# Node_Water.net
KiCad netlist of a schematic drawn in Altium Designer
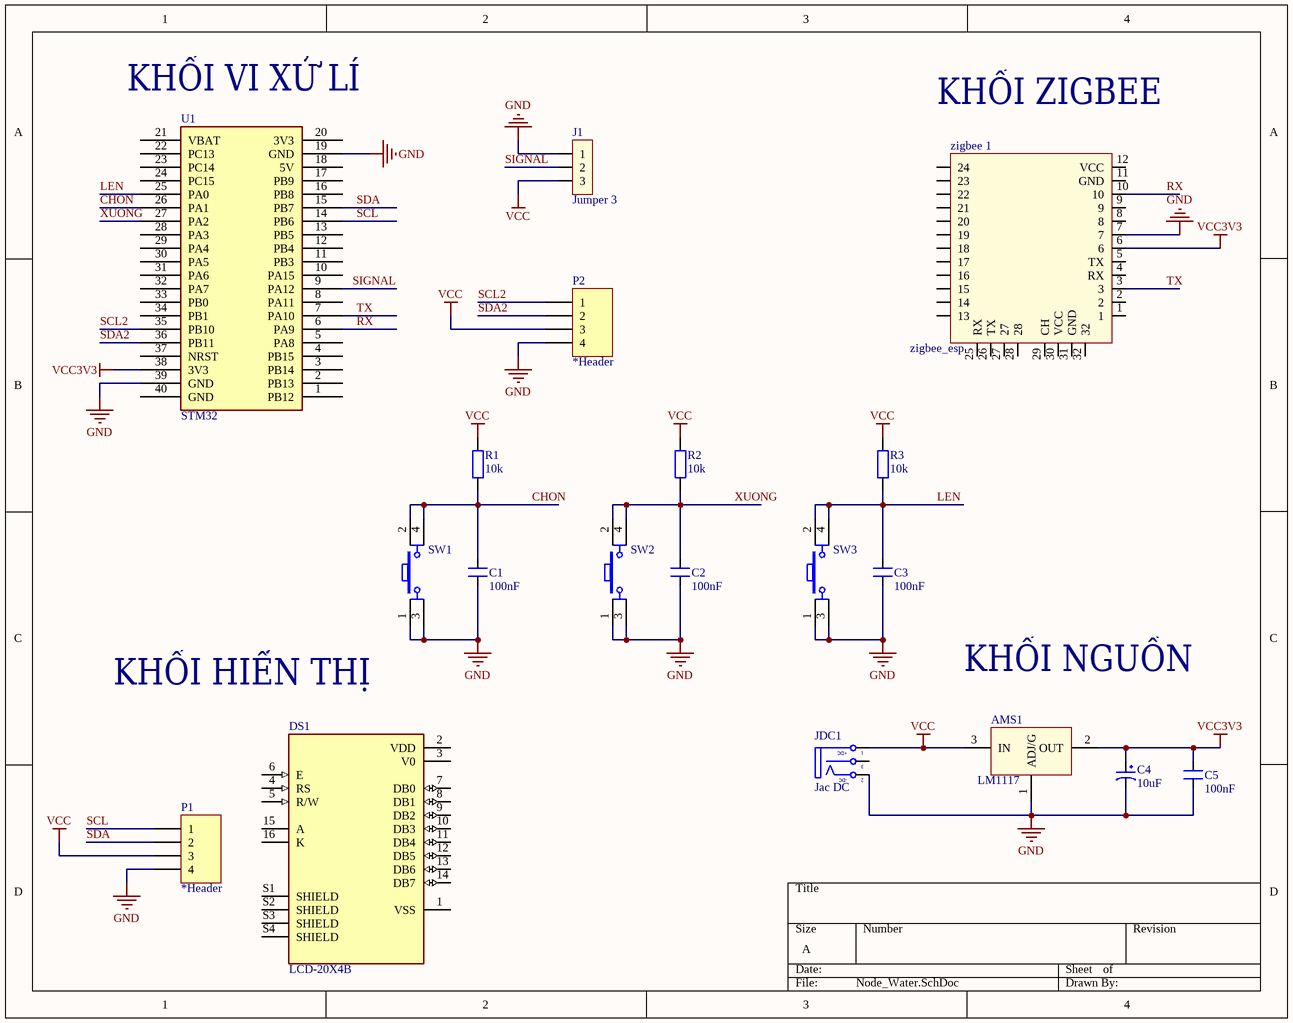
[diagram p0: Node_Water.SchDoc]

(export (version "E")
  (design (tool "Eeschema 10.0.6"))
  (components
    (comp (ref "AMS1")
      (value "LM1117")
      (footprint "SOT223-4N")
      (description "Available in 1.8V, 2.5V, 2.85V, 3.3V, 5V, and  Adjustable Versions")
      (libsource (lib "ACtoDC") (part "LM1117"))
    )
    (comp (ref "C1")
      (value "100nF")
      (footprint "CN1")
      (description "Cremic For Xtal 1pF => 100pF")
      (libsource (lib "syhaunguyen") (part "CN0"))
    )
    (comp (ref "C2")
      (value "100nF")
      (footprint "CN1")
      (description "Cremic For Xtal 1pF => 100pF")
      (libsource (lib "syhaunguyen") (part "CN0"))
    )
    (comp (ref "C3")
      (value "100nF")
      (footprint "CN1")
      (description "Cremic For Xtal 1pF => 100pF")
      (libsource (lib "syhaunguyen") (part "CN0"))
    )
    (comp (ref "C4")
      (value "10uF")
      (footprint "CP1/2")
      (description "Cap P  0,1uF < 22uF , 16 - 50V")
      (libsource (lib "VioletofSun") (part "CP1"))
    )
    (comp (ref "C5")
      (value "100nF")
      (footprint "CN1")
      (description "Cremic For Xtal 1pF => 100pF")
      (libsource (lib "syhaunguyen") (part "CN0"))
    )
    (comp (ref "DS1")
      (value "LCD-20X4B")
      (footprint "LCD_LCD-20X4B")
      (description "Display Development Tools 20X4 CHARACTER BLUE LCD W/BACKLIGHT")
      (fields (field (name "MF") "Gravitech"))
      (libsource (lib "LCD-20X4B") (part "LCD-20X4B"))
    )
    (comp (ref "J1") (value "Jumper 3") (footprint "JP3") (libsource (lib "syhaunguyen") (part "JP3")))
    (comp (ref "JDC1")
      (value "Jac DC")
      (footprint "DC-IN")
      (description "Jac DC input")
      (libsource (lib "syhaunguyen") (part "DCIN"))
    )
    (comp (ref "P1")
      (value "*Header")
      (footprint "HDR1X4")
      (description "Header, 4-Pin, Right Angle")
      (fields (field (name "PUBLISHER") "Altium Limited"))
      (libsource (lib "Cty1") (part "Header 4"))
    )
    (comp (ref "P2")
      (value "*Header")
      (footprint "HDR1X4")
      (description "Header, 4-Pin, Right Angle")
      (fields (field (name "PUBLISHER") "Altium Limited"))
      (libsource (lib "Cty1") (part "Header 4"))
    )
    (comp (ref "R1")
      (value "10k")
      (footprint "R1/4W")
      (description "Resistor 1/4W")
      (libsource (lib "syhaunguyen") (part "R1/4W"))
    )
    (comp (ref "R2")
      (value "10k")
      (footprint "R1/4W")
      (description "Resistor 1/4W")
      (libsource (lib "syhaunguyen") (part "R1/4W"))
    )
    (comp (ref "R3")
      (value "10k")
      (footprint "R1/4W")
      (description "Resistor 1/4W")
      (libsource (lib "syhaunguyen") (part "R1/4W"))
    )
    (comp (ref "SW1")
      (value "SW")
      (footprint "SW4")
      (description "Switch button 4 pin")
      (libsource (lib "syhaunguyen") (part "SW4"))
    )
    (comp (ref "SW2")
      (value "SW")
      (footprint "SW4")
      (description "Switch button 4 pin")
      (libsource (lib "syhaunguyen") (part "SW4"))
    )
    (comp (ref "SW3")
      (value "SW")
      (footprint "SW4")
      (description "Switch button 4 pin")
      (libsource (lib "syhaunguyen") (part "SW4"))
    )
    (comp (ref "U1")
      (value "STM32")
      (footprint "STM32")
      (libsource (lib "Other Microcontrollers") (part "STM32"))
    )
    (comp (ref "zigbee 1")
      (value "zigbee_esp")
      (footprint "zigbee")
      (libsource (lib "Main_stm8") (part "zigbee_esp"))
    )
  )
  (nets
    (net (code "2") (name "/CHON") (class "Default")
      (node (ref "C1") (pin "2") (pinfunction "2_2") (pintype "passive"))
      (node (ref "R1") (pin "1") (pinfunction "1_1") (pintype "passive"))
      (node (ref "SW1") (pin "2") (pintype "passive"))
      (node (ref "SW1") (pin "4") (pintype "passive"))
      (node (ref "U1") (pin "26") (pinfunction "PA1_26") (pintype "passive"))
    )
    (net (code "3") (name "/LEN") (class "Default")
      (node (ref "C3") (pin "2") (pinfunction "2_2") (pintype "passive"))
      (node (ref "R3") (pin "1") (pinfunction "1_1") (pintype "passive"))
      (node (ref "SW3") (pin "2") (pintype "passive"))
      (node (ref "SW3") (pin "4") (pintype "passive"))
      (node (ref "U1") (pin "25") (pinfunction "PA0_25") (pintype "passive"))
    )
    (net (code "4") (name "/RX") (class "Default")
      (node (ref "U1") (pin "6") (pinfunction "PA9_6") (pintype "passive"))
      (node (ref "zigbee 1") (pin "10") (pinfunction "10_10") (pintype "passive"))
    )
    (net (code "5") (name "/SCL") (class "Default")
      (node (ref "P1") (pin "1") (pinfunction "1_1") (pintype "passive"))
      (node (ref "U1") (pin "14") (pinfunction "PB6_14") (pintype "passive"))
    )
    (net (code "6") (name "/SCL2") (class "Default")
      (node (ref "P2") (pin "1") (pinfunction "1_1") (pintype "passive"))
      (node (ref "U1") (pin "35") (pinfunction "PB10_35") (pintype "passive"))
    )
    (net (code "7") (name "/SDA") (class "Default")
      (node (ref "P1") (pin "2") (pinfunction "2_2") (pintype "passive"))
      (node (ref "U1") (pin "15") (pinfunction "PB7_15") (pintype "passive"))
    )
    (net (code "8") (name "/SDA2") (class "Default")
      (node (ref "P2") (pin "2") (pinfunction "2_2") (pintype "passive"))
      (node (ref "U1") (pin "36") (pinfunction "PB11_36") (pintype "passive"))
    )
    (net (code "9") (name "/SIGNAL") (class "Default")
      (node (ref "J1") (pin "2") (pinfunction "2_2") (pintype "passive"))
      (node (ref "U1") (pin "9") (pinfunction "PA12_9") (pintype "passive"))
    )
    (net (code "10") (name "/TX") (class "Default")
      (node (ref "U1") (pin "7") (pinfunction "PA10_7") (pintype "passive"))
      (node (ref "zigbee 1") (pin "3") (pinfunction "3_3") (pintype "passive"))
    )
    (net (code "11") (name "/XUONG") (class "Default")
      (node (ref "C2") (pin "2") (pinfunction "2_2") (pintype "passive"))
      (node (ref "R2") (pin "1") (pinfunction "1_1") (pintype "passive"))
      (node (ref "SW2") (pin "2") (pintype "passive"))
      (node (ref "SW2") (pin "4") (pintype "passive"))
      (node (ref "U1") (pin "27") (pinfunction "PA2_27") (pintype "passive"))
    )
    (net (code "12") (name "GND") (class "Default")
      (node (ref "AMS1") (pin "1") (pinfunction "ADJ/G_1") (pintype "passive"))
      (node (ref "C1") (pin "1") (pinfunction "1_1") (pintype "passive"))
      (node (ref "C2") (pin "1") (pinfunction "1_1") (pintype "passive"))
      (node (ref "C3") (pin "1") (pinfunction "1_1") (pintype "passive"))
      (node (ref "C4") (pin "2") (pinfunction "2_2") (pintype "passive"))
      (node (ref "C5") (pin "1") (pinfunction "1_1") (pintype "passive"))
      (node (ref "J1") (pin "1") (pinfunction "1_1") (pintype "passive"))
      (node (ref "JDC1") (pin "2") (pinfunction "TN_2") (pintype "passive"))
      (node (ref "P1") (pin "4") (pinfunction "4_4") (pintype "passive"))
      (node (ref "P2") (pin "4") (pinfunction "4_4") (pintype "passive"))
      (node (ref "SW1") (pin "1") (pintype "passive"))
      (node (ref "SW1") (pin "3") (pintype "passive"))
      (node (ref "SW2") (pin "1") (pintype "passive"))
      (node (ref "SW2") (pin "3") (pintype "passive"))
      (node (ref "SW3") (pin "1") (pintype "passive"))
      (node (ref "SW3") (pin "3") (pintype "passive"))
      (node (ref "U1") (pin "19") (pinfunction "GND_19") (pintype "passive"))
      (node (ref "U1") (pin "39") (pinfunction "GND_39") (pintype "passive"))
      (node (ref "zigbee 1") (pin "7") (pinfunction "7_7") (pintype "passive"))
    )
    (net (code "13") (name "VCC") (class "Default")
      (node (ref "AMS1") (pin "3") (pinfunction "IN_3") (pintype "passive"))
      (node (ref "J1") (pin "3") (pinfunction "3_3") (pintype "passive"))
      (node (ref "JDC1") (pin "1") (pinfunction "T_1") (pintype "passive"))
      (node (ref "P1") (pin "3") (pinfunction "3_3") (pintype "passive"))
      (node (ref "P2") (pin "3") (pinfunction "3_3") (pintype "passive"))
      (node (ref "R1") (pin "2") (pinfunction "2_2") (pintype "passive"))
      (node (ref "R2") (pin "2") (pinfunction "2_2") (pintype "passive"))
      (node (ref "R3") (pin "2") (pinfunction "2_2") (pintype "passive"))
    )
    (net (code "14") (name "VCC3V3") (class "Default")
      (node (ref "AMS1") (pin "2") (pinfunction "OUT_2") (pintype "passive"))
      (node (ref "C4") (pin "1") (pinfunction "1_1") (pintype "passive"))
      (node (ref "C5") (pin "2") (pinfunction "2_2") (pintype "passive"))
      (node (ref "U1") (pin "38") (pinfunction "3V3_38") (pintype "passive"))
      (node (ref "zigbee 1") (pin "6") (pinfunction "6_6") (pintype "passive"))
    )
    (net (code "15") (name "unconnected-(DS1-A-Pad15)") (class "Default")
      (node (ref "DS1") (pin "15") (pinfunction "A_15") (pintype "passive"))
    )
    (net (code "16") (name "unconnected-(DS1-DB0-Pad7)") (class "Default")
      (node (ref "DS1") (pin "7") (pinfunction "DB0_7") (pintype "bidirectional"))
    )
    (net (code "17") (name "unconnected-(DS1-DB1-Pad8)") (class "Default")
      (node (ref "DS1") (pin "8") (pinfunction "DB1_8") (pintype "bidirectional"))
    )
    (net (code "18") (name "unconnected-(DS1-DB2-Pad9)") (class "Default")
      (node (ref "DS1") (pin "9") (pinfunction "DB2_9") (pintype "bidirectional"))
    )
    (net (code "19") (name "unconnected-(DS1-DB3-Pad10)") (class "Default")
      (node (ref "DS1") (pin "10") (pinfunction "DB3_10") (pintype "bidirectional"))
    )
    (net (code "20") (name "unconnected-(DS1-DB4-Pad11)") (class "Default")
      (node (ref "DS1") (pin "11") (pinfunction "DB4_11") (pintype "bidirectional"))
    )
    (net (code "21") (name "unconnected-(DS1-DB5-Pad12)") (class "Default")
      (node (ref "DS1") (pin "12") (pinfunction "DB5_12") (pintype "bidirectional"))
    )
    (net (code "22") (name "unconnected-(DS1-DB6-Pad13)") (class "Default")
      (node (ref "DS1") (pin "13") (pinfunction "DB6_13") (pintype "bidirectional"))
    )
    (net (code "23") (name "unconnected-(DS1-DB7-Pad14)") (class "Default")
      (node (ref "DS1") (pin "14") (pinfunction "DB7_14") (pintype "bidirectional"))
    )
    (net (code "24") (name "unconnected-(DS1-E-Pad6)") (class "Default")
      (node (ref "DS1") (pin "6") (pinfunction "E_6") (pintype "input"))
    )
    (net (code "25") (name "unconnected-(DS1-K-Pad16)") (class "Default")
      (node (ref "DS1") (pin "16") (pinfunction "K_16") (pintype "passive"))
    )
    (net (code "26") (name "unconnected-(DS1-RS-Pad4)") (class "Default")
      (node (ref "DS1") (pin "4") (pinfunction "RS_4") (pintype "input"))
    )
    (net (code "27") (name "unconnected-(DS1-R{slash}W-Pad5)") (class "Default")
      (node (ref "DS1") (pin "5") (pinfunction "R/W_5") (pintype "input"))
    )
    (net (code "28") (name "unconnected-(DS1-SHIELD-PadS1)") (class "Default")
      (node (ref "DS1") (pin "S1") (pinfunction "SHIELD_S1") (pintype "passive"))
    )
    (net (code "29") (name "unconnected-(DS1-SHIELD-PadS2)") (class "Default")
      (node (ref "DS1") (pin "S2") (pinfunction "SHIELD_S2") (pintype "passive"))
    )
    (net (code "30") (name "unconnected-(DS1-SHIELD-PadS3)") (class "Default")
      (node (ref "DS1") (pin "S3") (pinfunction "SHIELD_S3") (pintype "passive"))
    )
    (net (code "31") (name "unconnected-(DS1-SHIELD-PadS4)") (class "Default")
      (node (ref "DS1") (pin "S4") (pinfunction "SHIELD_S4") (pintype "passive"))
    )
    (net (code "32") (name "unconnected-(DS1-V0-Pad3)") (class "Default")
      (node (ref "DS1") (pin "3") (pinfunction "V0_3") (pintype "power_in"))
    )
    (net (code "33") (name "unconnected-(DS1-VDD-Pad2)") (class "Default")
      (node (ref "DS1") (pin "2") (pinfunction "VDD_2") (pintype "power_in"))
    )
    (net (code "34") (name "unconnected-(DS1-VSS-Pad1)") (class "Default")
      (node (ref "DS1") (pin "1") (pinfunction "VSS_1") (pintype "power_in"))
    )
    (net (code "35") (name "unconnected-(JDC1-S-Pad3)") (class "Default")
      (node (ref "JDC1") (pin "3") (pinfunction "S_3") (pintype "power_in"))
    )
    (net (code "36") (name "unconnected-(U1-3V3-Pad20)") (class "Default")
      (node (ref "U1") (pin "20") (pinfunction "3V3_20") (pintype "passive"))
    )
    (net (code "37") (name "unconnected-(U1-5V-Pad18)") (class "Default")
      (node (ref "U1") (pin "18") (pinfunction "5V_18") (pintype "passive"))
    )
    (net (code "38") (name "unconnected-(U1-GND-Pad40)") (class "Default")
      (node (ref "U1") (pin "40") (pinfunction "GND_40") (pintype "passive"))
    )
    (net (code "39") (name "unconnected-(U1-NRST-Pad37)") (class "Default")
      (node (ref "U1") (pin "37") (pinfunction "NRST_37") (pintype "passive"))
    )
    (net (code "40") (name "unconnected-(U1-PA3-Pad28)") (class "Default")
      (node (ref "U1") (pin "28") (pinfunction "PA3_28") (pintype "passive"))
    )
    (net (code "41") (name "unconnected-(U1-PA4-Pad29)") (class "Default")
      (node (ref "U1") (pin "29") (pinfunction "PA4_29") (pintype "passive"))
    )
    (net (code "42") (name "unconnected-(U1-PA5-Pad30)") (class "Default")
      (node (ref "U1") (pin "30") (pinfunction "PA5_30") (pintype "passive"))
    )
    (net (code "43") (name "unconnected-(U1-PA6-Pad31)") (class "Default")
      (node (ref "U1") (pin "31") (pinfunction "PA6_31") (pintype "passive"))
    )
    (net (code "44") (name "unconnected-(U1-PA7-Pad32)") (class "Default")
      (node (ref "U1") (pin "32") (pinfunction "PA7_32") (pintype "passive"))
    )
    (net (code "45") (name "unconnected-(U1-PA8-Pad5)") (class "Default")
      (node (ref "U1") (pin "5") (pinfunction "PA8_5") (pintype "passive"))
    )
    (net (code "46") (name "unconnected-(U1-PA11-Pad8)") (class "Default")
      (node (ref "U1") (pin "8") (pinfunction "PA11_8") (pintype "passive"))
    )
    (net (code "47") (name "unconnected-(U1-PA15-Pad10)") (class "Default")
      (node (ref "U1") (pin "10") (pinfunction "PA15_10") (pintype "passive"))
    )
    (net (code "48") (name "unconnected-(U1-PB0-Pad33)") (class "Default")
      (node (ref "U1") (pin "33") (pinfunction "PB0_33") (pintype "passive"))
    )
    (net (code "49") (name "unconnected-(U1-PB1-Pad34)") (class "Default")
      (node (ref "U1") (pin "34") (pinfunction "PB1_34") (pintype "passive"))
    )
    (net (code "50") (name "unconnected-(U1-PB3-Pad11)") (class "Default")
      (node (ref "U1") (pin "11") (pinfunction "PB3_11") (pintype "passive"))
    )
    (net (code "51") (name "unconnected-(U1-PB4-Pad12)") (class "Default")
      (node (ref "U1") (pin "12") (pinfunction "PB4_12") (pintype "passive"))
    )
    (net (code "52") (name "unconnected-(U1-PB5-Pad13)") (class "Default")
      (node (ref "U1") (pin "13") (pinfunction "PB5_13") (pintype "passive"))
    )
    (net (code "53") (name "unconnected-(U1-PB8-Pad16)") (class "Default")
      (node (ref "U1") (pin "16") (pinfunction "PB8_16") (pintype "passive"))
    )
    (net (code "54") (name "unconnected-(U1-PB9-Pad17)") (class "Default")
      (node (ref "U1") (pin "17") (pinfunction "PB9_17") (pintype "passive"))
    )
    (net (code "55") (name "unconnected-(U1-PB12-Pad1)") (class "Default")
      (node (ref "U1") (pin "1") (pinfunction "PB12_1") (pintype "passive"))
    )
    (net (code "56") (name "unconnected-(U1-PB13-Pad2)") (class "Default")
      (node (ref "U1") (pin "2") (pinfunction "PB13_2") (pintype "passive"))
    )
    (net (code "57") (name "unconnected-(U1-PB14-Pad3)") (class "Default")
      (node (ref "U1") (pin "3") (pinfunction "PB14_3") (pintype "passive"))
    )
    (net (code "58") (name "unconnected-(U1-PB15-Pad4)") (class "Default")
      (node (ref "U1") (pin "4") (pinfunction "PB15_4") (pintype "passive"))
    )
    (net (code "59") (name "unconnected-(U1-PC13-Pad22)") (class "Default")
      (node (ref "U1") (pin "22") (pinfunction "PC13_22") (pintype "passive"))
    )
    (net (code "60") (name "unconnected-(U1-PC14-Pad23)") (class "Default")
      (node (ref "U1") (pin "23") (pinfunction "PC14_23") (pintype "passive"))
    )
    (net (code "61") (name "unconnected-(U1-PC15-Pad24)") (class "Default")
      (node (ref "U1") (pin "24") (pinfunction "PC15_24") (pintype "passive"))
    )
    (net (code "62") (name "unconnected-(U1-VBAT-Pad21)") (class "Default")
      (node (ref "U1") (pin "21") (pinfunction "VBAT_21") (pintype "passive"))
    )
    (net (code "63") (name "unconnected-(zigbee 1-CH-Pad29)") (class "Default")
      (node (ref "zigbee 1") (pin "29") (pinfunction "CH_29") (pintype "passive"))
    )
    (net (code "64") (name "unconnected-(zigbee 1-GND-Pad11)") (class "Default")
      (node (ref "zigbee 1") (pin "11") (pinfunction "GND_11") (pintype "passive"))
    )
    (net (code "65") (name "unconnected-(zigbee 1-GND-Pad31)") (class "Default")
      (node (ref "zigbee 1") (pin "31") (pinfunction "GND_31") (pintype "passive"))
    )
    (net (code "66") (name "unconnected-(zigbee 1-Pad1)") (class "Default")
      (node (ref "zigbee 1") (pin "1") (pinfunction "1_1") (pintype "passive"))
    )
    (net (code "67") (name "unconnected-(zigbee 1-Pad2)") (class "Default")
      (node (ref "zigbee 1") (pin "2") (pinfunction "2_2") (pintype "passive"))
    )
    (net (code "68") (name "unconnected-(zigbee 1-Pad8)") (class "Default")
      (node (ref "zigbee 1") (pin "8") (pinfunction "8_8") (pintype "passive"))
    )
    (net (code "69") (name "unconnected-(zigbee 1-Pad9)") (class "Default")
      (node (ref "zigbee 1") (pin "9") (pinfunction "9_9") (pintype "passive"))
    )
    (net (code "70") (name "unconnected-(zigbee 1-Pad13)") (class "Default")
      (node (ref "zigbee 1") (pin "13") (pinfunction "13_13") (pintype "passive"))
    )
    (net (code "71") (name "unconnected-(zigbee 1-Pad14)") (class "Default")
      (node (ref "zigbee 1") (pin "14") (pinfunction "14_14") (pintype "passive"))
    )
    (net (code "72") (name "unconnected-(zigbee 1-Pad15)") (class "Default")
      (node (ref "zigbee 1") (pin "15") (pinfunction "15_15") (pintype "passive"))
    )
    (net (code "73") (name "unconnected-(zigbee 1-Pad16)") (class "Default")
      (node (ref "zigbee 1") (pin "16") (pinfunction "16_16") (pintype "passive"))
    )
    (net (code "74") (name "unconnected-(zigbee 1-Pad17)") (class "Default")
      (node (ref "zigbee 1") (pin "17") (pinfunction "17_17") (pintype "passive"))
    )
    (net (code "75") (name "unconnected-(zigbee 1-Pad18)") (class "Default")
      (node (ref "zigbee 1") (pin "18") (pinfunction "18_18") (pintype "passive"))
    )
    (net (code "76") (name "unconnected-(zigbee 1-Pad19)") (class "Default")
      (node (ref "zigbee 1") (pin "19") (pinfunction "19_19") (pintype "passive"))
    )
    (net (code "77") (name "unconnected-(zigbee 1-Pad20)") (class "Default")
      (node (ref "zigbee 1") (pin "20") (pinfunction "20_20") (pintype "passive"))
    )
    (net (code "78") (name "unconnected-(zigbee 1-Pad21)") (class "Default")
      (node (ref "zigbee 1") (pin "21") (pinfunction "21_21") (pintype "passive"))
    )
    (net (code "79") (name "unconnected-(zigbee 1-Pad22)") (class "Default")
      (node (ref "zigbee 1") (pin "22") (pinfunction "22_22") (pintype "passive"))
    )
    (net (code "80") (name "unconnected-(zigbee 1-Pad23)") (class "Default")
      (node (ref "zigbee 1") (pin "23") (pinfunction "23_23") (pintype "passive"))
    )
    (net (code "81") (name "unconnected-(zigbee 1-Pad24)") (class "Default")
      (node (ref "zigbee 1") (pin "24") (pinfunction "24_24") (pintype "passive"))
    )
    (net (code "82") (name "unconnected-(zigbee 1-Pad27)") (class "Default")
      (node (ref "zigbee 1") (pin "27") (pinfunction "27_27") (pintype "passive"))
    )
    (net (code "83") (name "unconnected-(zigbee 1-Pad28)") (class "Default")
      (node (ref "zigbee 1") (pin "28") (pinfunction "28_28") (pintype "passive"))
    )
    (net (code "84") (name "unconnected-(zigbee 1-Pad32)") (class "Default")
      (node (ref "zigbee 1") (pin "32") (pinfunction "32_32") (pintype "passive"))
    )
    (net (code "85") (name "unconnected-(zigbee 1-RX-Pad4)") (class "Default")
      (node (ref "zigbee 1") (pin "4") (pinfunction "RX_4") (pintype "passive"))
    )
    (net (code "86") (name "unconnected-(zigbee 1-RX-Pad25)") (class "Default")
      (node (ref "zigbee 1") (pin "25") (pinfunction "RX_25") (pintype "passive"))
    )
    (net (code "87") (name "unconnected-(zigbee 1-TX-Pad5)") (class "Default")
      (node (ref "zigbee 1") (pin "5") (pinfunction "TX_5") (pintype "passive"))
    )
    (net (code "88") (name "unconnected-(zigbee 1-TX-Pad26)") (class "Default")
      (node (ref "zigbee 1") (pin "26") (pinfunction "TX_26") (pintype "passive"))
    )
    (net (code "89") (name "unconnected-(zigbee 1-VCC-Pad12)") (class "Default")
      (node (ref "zigbee 1") (pin "12") (pinfunction "VCC_12") (pintype "passive"))
    )
    (net (code "90") (name "unconnected-(zigbee 1-VCC-Pad30)") (class "Default")
      (node (ref "zigbee 1") (pin "30") (pinfunction "VCC_30") (pintype "passive"))
    )
  )
)
